# USB_to_Serial.net
KiCad netlist of a schematic drawn in Altium Designer
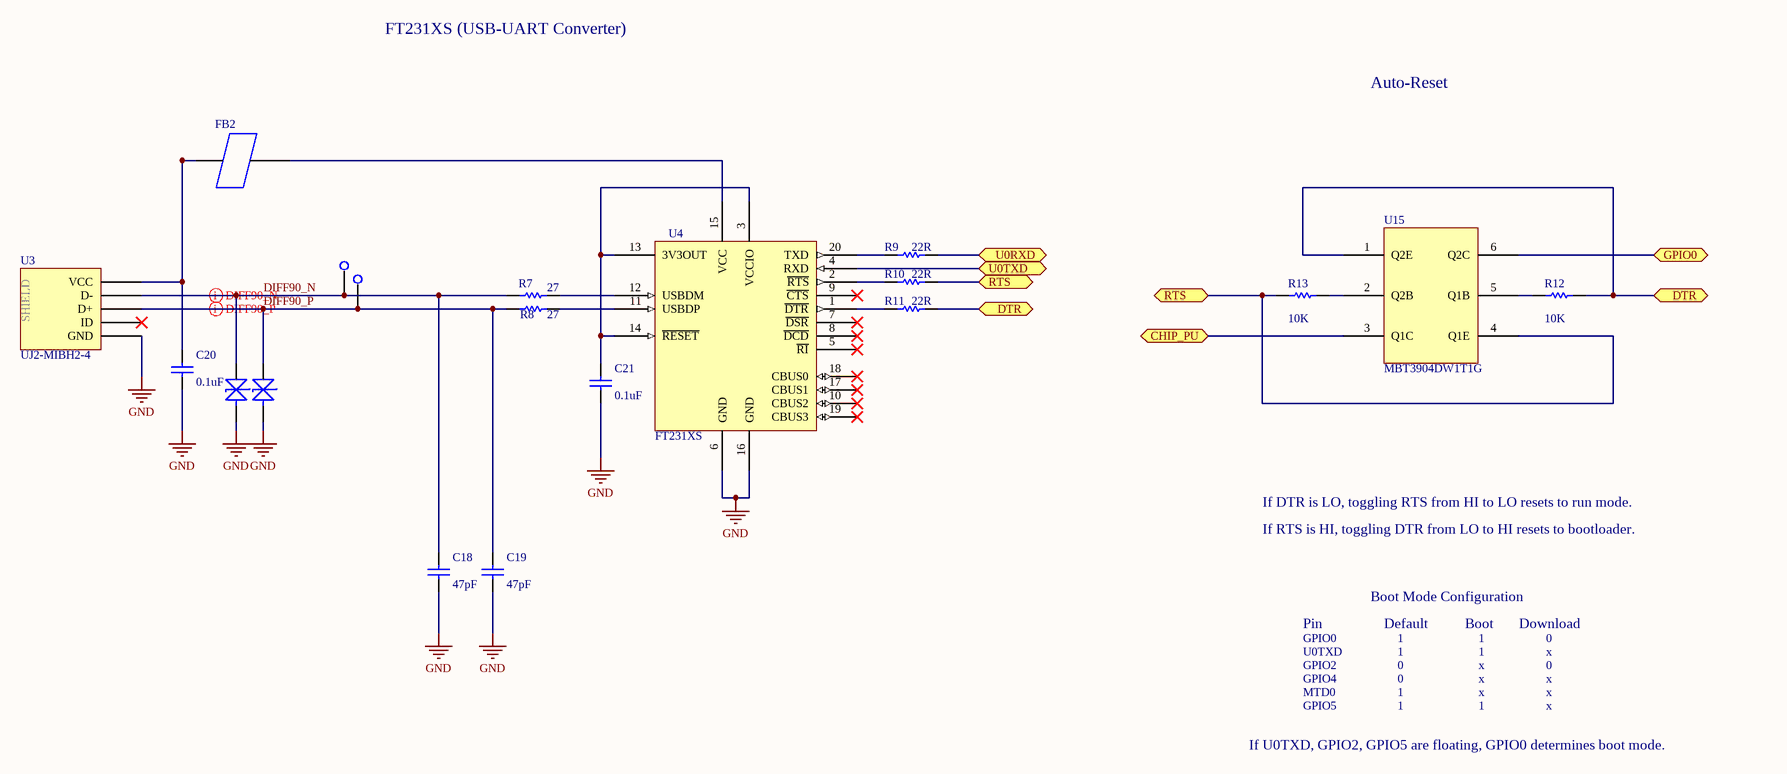
[diagram p0: USB to Serial.SchDoc]

(export (version "E")
  (design (tool "Eeschema 10.0.6"))
  (components
    (comp (ref "C18")
      (value "47pF")
      (footprint "1608[0603]")
      (description "Capacitor")
      (fields (field (name "Comment") "Cap") (field (name "PUBLISHER") "Altium Limited"))
      (libsource (lib "Miscellaneous Devices") (part "Cap"))
    )
    (comp (ref "C19")
      (value "47pF")
      (footprint "1608[0603]")
      (description "Capacitor")
      (fields (field (name "Comment") "Cap") (field (name "PUBLISHER") "Altium Limited"))
      (libsource (lib "Miscellaneous Devices") (part "Cap"))
    )
    (comp (ref "C20")
      (value "0.1uF")
      (footprint "1608[0603]")
      (description "Capacitor")
      (fields (field (name "Comment") "Cap") (field (name "PUBLISHER") "Altium Limited"))
      (libsource (lib "Miscellaneous Devices") (part "Cap"))
    )
    (comp (ref "C21")
      (value "0.1uF")
      (footprint "1608[0603]")
      (description "Capacitor")
      (fields (field (name "Comment") "Cap") (field (name "PUBLISHER") "Altium Limited"))
      (libsource (lib "Miscellaneous Devices") (part "Cap"))
    )
    (comp (ref "D2")
      (value "ESD7951ST5GOSCT-ND")
      (footprint "SODFL100X40-2N")
      (description "TVS Diode")
      (libsource (lib "Gas Monitor Components") (part "ESD7951S"))
    )
    (comp (ref "D3")
      (value "ESD7951ST5GOSCT-ND")
      (footprint "SODFL100X40-2N")
      (description "TVS Diode")
      (libsource (lib "Gas Monitor Components") (part "ESD7951S"))
    )
    (comp (ref "FB2")
      (value "Ferrite Bead")
      (footprint "MI0805K400R-10")
      (description "MI0805K400R-10")
      (libsource (lib "Gas Monitor Components") (part "Ferrite Bead"))
    )
    (comp (ref "R7")
      (value "27")
      (footprint "6-0805_N")
      (description "Resistor")
      (fields (field (name "Comment") "Res1") (field (name "PUBLISHER") "Altium Limited"))
      (libsource (lib "Miscellaneous Devices") (part "Res1"))
    )
    (comp (ref "R8")
      (value "27")
      (footprint "6-0805_N")
      (description "Resistor")
      (fields (field (name "Comment") "Res1") (field (name "PUBLISHER") "Altium Limited"))
      (libsource (lib "Miscellaneous Devices") (part "Res1"))
    )
    (comp (ref "R9")
      (value "22R")
      (footprint "6-0805_N")
      (description "Resistor")
      (fields (field (name "Comment") "Res1") (field (name "PUBLISHER") "Altium Limited"))
      (libsource (lib "Miscellaneous Devices") (part "Res1"))
    )
    (comp (ref "R10")
      (value "22R")
      (footprint "6-0805_N")
      (description "Resistor")
      (fields (field (name "Comment") "Res1") (field (name "PUBLISHER") "Altium Limited"))
      (libsource (lib "Miscellaneous Devices") (part "Res1"))
    )
    (comp (ref "R11")
      (value "22R")
      (footprint "6-0805_N")
      (description "Resistor")
      (fields (field (name "Comment") "Res1") (field (name "PUBLISHER") "Altium Limited"))
      (libsource (lib "Miscellaneous Devices") (part "Res1"))
    )
    (comp (ref "R12")
      (value "10K")
      (footprint "6-0805_N")
      (description "Resistor")
      (fields (field (name "Comment") "Res1") (field (name "PUBLISHER") "Altium Limited"))
      (libsource (lib "Miscellaneous Devices") (part "Res1"))
    )
    (comp (ref "R13")
      (value "10K")
      (footprint "6-0805_N")
      (description "Resistor")
      (fields (field (name "Comment") "Res1") (field (name "PUBLISHER") "Altium Limited"))
      (libsource (lib "Miscellaneous Devices") (part "Res1"))
    )
    (comp (ref "TP25")
      (value "SMD Compact Test Point")
      (footprint "5029 Test Point")
      (libsource (lib "Gas Monitor Components") (part "SMD Compact Test Point"))
    )
    (comp (ref "TP26")
      (value "SMD Compact Test Point")
      (footprint "5029 Test Point")
      (libsource (lib "Gas Monitor Components") (part "SMD Compact Test Point"))
    )
    (comp (ref "U3")
      (value "UJ2-MIBH2-4")
      (footprint "UJ2-MIBH2-4-SMT")
      (libsource (lib "Gas Monitor Components") (part "USB Shield"))
    )
    (comp (ref "U4")
      (value "FT231XS")
      (footprint "SOP64P1030X175-20N")
      (description "USB-UART Interface")
      (libsource (lib "Gas Monitor Components") (part "FT231XS"))
    )
    (comp (ref "U15")
      (value "MBT3904DW1T1G")
      (footprint "SOT65P210X110-6N")
      (description "Dual NPN Transistors")
      (libsource (lib "Gas Monitor Components") (part "MBT3904DW1"))
    )
  )
  (nets
    (net (code "1") (name "/CHIP_PU") (class "Default")
      (node (ref "U15") (pin "3") (pinfunction "Q1C_3") (pintype "passive"))
    )
    (net (code "2") (name "/DIFF90_N") (class "Default")
      (node (ref "C18") (pin "2") (pinfunction "2_2") (pintype "passive"))
      (node (ref "D2") (pin "2") (pinfunction "ANODE_2") (pintype "passive"))
      (node (ref "R7") (pin "1") (pinfunction "1_1") (pintype "passive"))
      (node (ref "TP26") (pin "1") (pinfunction "1_1") (pintype "passive"))
      (node (ref "U3") (pin "2") (pinfunction "D-_2") (pintype "passive"))
    )
    (net (code "3") (name "/DIFF90_P") (class "Default")
      (node (ref "C19") (pin "2") (pinfunction "2_2") (pintype "passive"))
      (node (ref "D3") (pin "2") (pinfunction "ANODE_2") (pintype "passive"))
      (node (ref "R8") (pin "1") (pinfunction "1_1") (pintype "passive"))
      (node (ref "TP25") (pin "1") (pinfunction "1_1") (pintype "passive"))
      (node (ref "U3") (pin "3") (pinfunction "D+_3") (pintype "passive"))
    )
    (net (code "4") (name "/DTR") (class "Default")
      (node (ref "R11") (pin "2") (pinfunction "2_2") (pintype "passive"))
      (node (ref "R12") (pin "2") (pinfunction "2_2") (pintype "passive"))
      (node (ref "U15") (pin "1") (pinfunction "Q2E_1") (pintype "passive"))
    )
    (net (code "5") (name "/GPIO0") (class "Default")
      (node (ref "U15") (pin "6") (pinfunction "Q2C_6") (pintype "passive"))
    )
    (net (code "6") (name "/RTS") (class "Default")
      (node (ref "R10") (pin "2") (pinfunction "2_2") (pintype "passive"))
      (node (ref "R13") (pin "1") (pinfunction "1_1") (pintype "passive"))
      (node (ref "U15") (pin "4") (pinfunction "Q1E_4") (pintype "passive"))
    )
    (net (code "7") (name "/U0RXD") (class "Default")
      (node (ref "R9") (pin "2") (pinfunction "2_2") (pintype "passive"))
    )
    (net (code "8") (name "/U0TXD") (class "Default")
      (node (ref "U4") (pin "4") (pinfunction "RXD_4") (pintype "input"))
    )
    (net (code "9") (name "GND") (class "Default")
      (node (ref "C18") (pin "1") (pinfunction "1_1") (pintype "passive"))
      (node (ref "C19") (pin "1") (pinfunction "1_1") (pintype "passive"))
      (node (ref "C20") (pin "1") (pinfunction "1_1") (pintype "passive"))
      (node (ref "C21") (pin "1") (pinfunction "1_1") (pintype "passive"))
      (node (ref "D2") (pin "1") (pinfunction "CATHODE_1") (pintype "passive"))
      (node (ref "D3") (pin "1") (pinfunction "CATHODE_1") (pintype "passive"))
      (node (ref "U3") (pin "5") (pinfunction "GND_5") (pintype "power_in"))
      (node (ref "U4") (pin "16") (pinfunction "GND_16") (pintype "power_in"))
      (node (ref "U4") (pin "6") (pinfunction "GND_6") (pintype "power_in"))
    )
    (net (code "10") (name "Net-(U3-VCC)") (class "Default")
      (node (ref "C20") (pin "2") (pinfunction "2_2") (pintype "passive"))
      (node (ref "FB2") (pin "1") (pinfunction "1_1") (pintype "passive"))
      (node (ref "U3") (pin "1") (pinfunction "VCC_1") (pintype "power_in"))
    )
    (net (code "11") (name "Net-(U4-3V3OUT)") (class "Default")
      (node (ref "C21") (pin "2") (pinfunction "2_2") (pintype "passive"))
      (node (ref "U4") (pin "13") (pinfunction "3V3OUT_13") (pintype "power_in"))
      (node (ref "U4") (pin "14") (pinfunction "~{RESET}_14") (pintype "input"))
      (node (ref "U4") (pin "3") (pinfunction "VCCIO_3") (pintype "passive"))
    )
    (net (code "12") (name "Net-(U4-TXD)") (class "Default")
      (node (ref "R9") (pin "1") (pinfunction "1_1") (pintype "passive"))
      (node (ref "U4") (pin "20") (pinfunction "TXD_20") (pintype "output"))
    )
    (net (code "13") (name "Net-(U4-USBDM)") (class "Default")
      (node (ref "R7") (pin "2") (pinfunction "2_2") (pintype "passive"))
      (node (ref "U4") (pin "12") (pinfunction "USBDM_12") (pintype "input"))
    )
    (net (code "14") (name "Net-(U4-USBDP)") (class "Default")
      (node (ref "R8") (pin "2") (pinfunction "2_2") (pintype "passive"))
      (node (ref "U4") (pin "11") (pinfunction "USBDP_11") (pintype "input"))
    )
    (net (code "15") (name "Net-(U4-VCC)") (class "Default")
      (node (ref "FB2") (pin "2") (pinfunction "2_2") (pintype "passive"))
      (node (ref "U4") (pin "15") (pinfunction "VCC_15") (pintype "power_in"))
    )
    (net (code "16") (name "Net-(U4-~{DTR})") (class "Default")
      (node (ref "R11") (pin "1") (pinfunction "1_1") (pintype "passive"))
      (node (ref "U4") (pin "1") (pinfunction "~{DTR}_1") (pintype "output"))
    )
    (net (code "17") (name "Net-(U4-~{RTS})") (class "Default")
      (node (ref "R10") (pin "1") (pinfunction "1_1") (pintype "passive"))
      (node (ref "U4") (pin "2") (pinfunction "~{RTS}_2") (pintype "output"))
    )
    (net (code "18") (name "Net-(U15-Q1B)") (class "Default")
      (node (ref "R12") (pin "1") (pinfunction "1_1") (pintype "passive"))
      (node (ref "U15") (pin "5") (pinfunction "Q1B_5") (pintype "passive"))
    )
    (net (code "19") (name "Net-(U15-Q2B)") (class "Default")
      (node (ref "R13") (pin "2") (pinfunction "2_2") (pintype "passive"))
      (node (ref "U15") (pin "2") (pinfunction "Q2B_2") (pintype "passive"))
    )
    (net (code "20") (name "unconnected-(U3-ID-Pad4)") (class "Default")
      (node (ref "U3") (pin "4") (pinfunction "ID_4") (pintype "passive+no_connect"))
    )
    (net (code "21") (name "unconnected-(U4-CBUS0-Pad18)") (class "Default")
      (node (ref "U4") (pin "18") (pinfunction "CBUS0_18") (pintype "bidirectional+no_connect"))
    )
    (net (code "22") (name "unconnected-(U4-CBUS1-Pad17)") (class "Default")
      (node (ref "U4") (pin "17") (pinfunction "CBUS1_17") (pintype "bidirectional+no_connect"))
    )
    (net (code "23") (name "unconnected-(U4-CBUS2-Pad10)") (class "Default")
      (node (ref "U4") (pin "10") (pinfunction "CBUS2_10") (pintype "bidirectional+no_connect"))
    )
    (net (code "24") (name "unconnected-(U4-CBUS3-Pad19)") (class "Default")
      (node (ref "U4") (pin "19") (pinfunction "CBUS3_19") (pintype "bidirectional+no_connect"))
    )
    (net (code "25") (name "unconnected-(U4-~{CTS}-Pad9)") (class "Default")
      (node (ref "U4") (pin "9") (pinfunction "~{CTS}_9") (pintype "passive+no_connect"))
    )
    (net (code "26") (name "unconnected-(U4-~{DCD}-Pad8)") (class "Default")
      (node (ref "U4") (pin "8") (pinfunction "~{DCD}_8") (pintype "passive+no_connect"))
    )
    (net (code "27") (name "unconnected-(U4-~{DSR}-Pad7)") (class "Default")
      (node (ref "U4") (pin "7") (pinfunction "~{DSR}_7") (pintype "passive+no_connect"))
    )
    (net (code "28") (name "unconnected-(U4-~{RI}-Pad5)") (class "Default")
      (node (ref "U4") (pin "5") (pinfunction "~{RI}_5") (pintype "passive+no_connect"))
    )
  )
)
